# ArcadeRpiSmartShield_33_MCU.net
KiCad netlist of a schematic drawn in Altium Designer
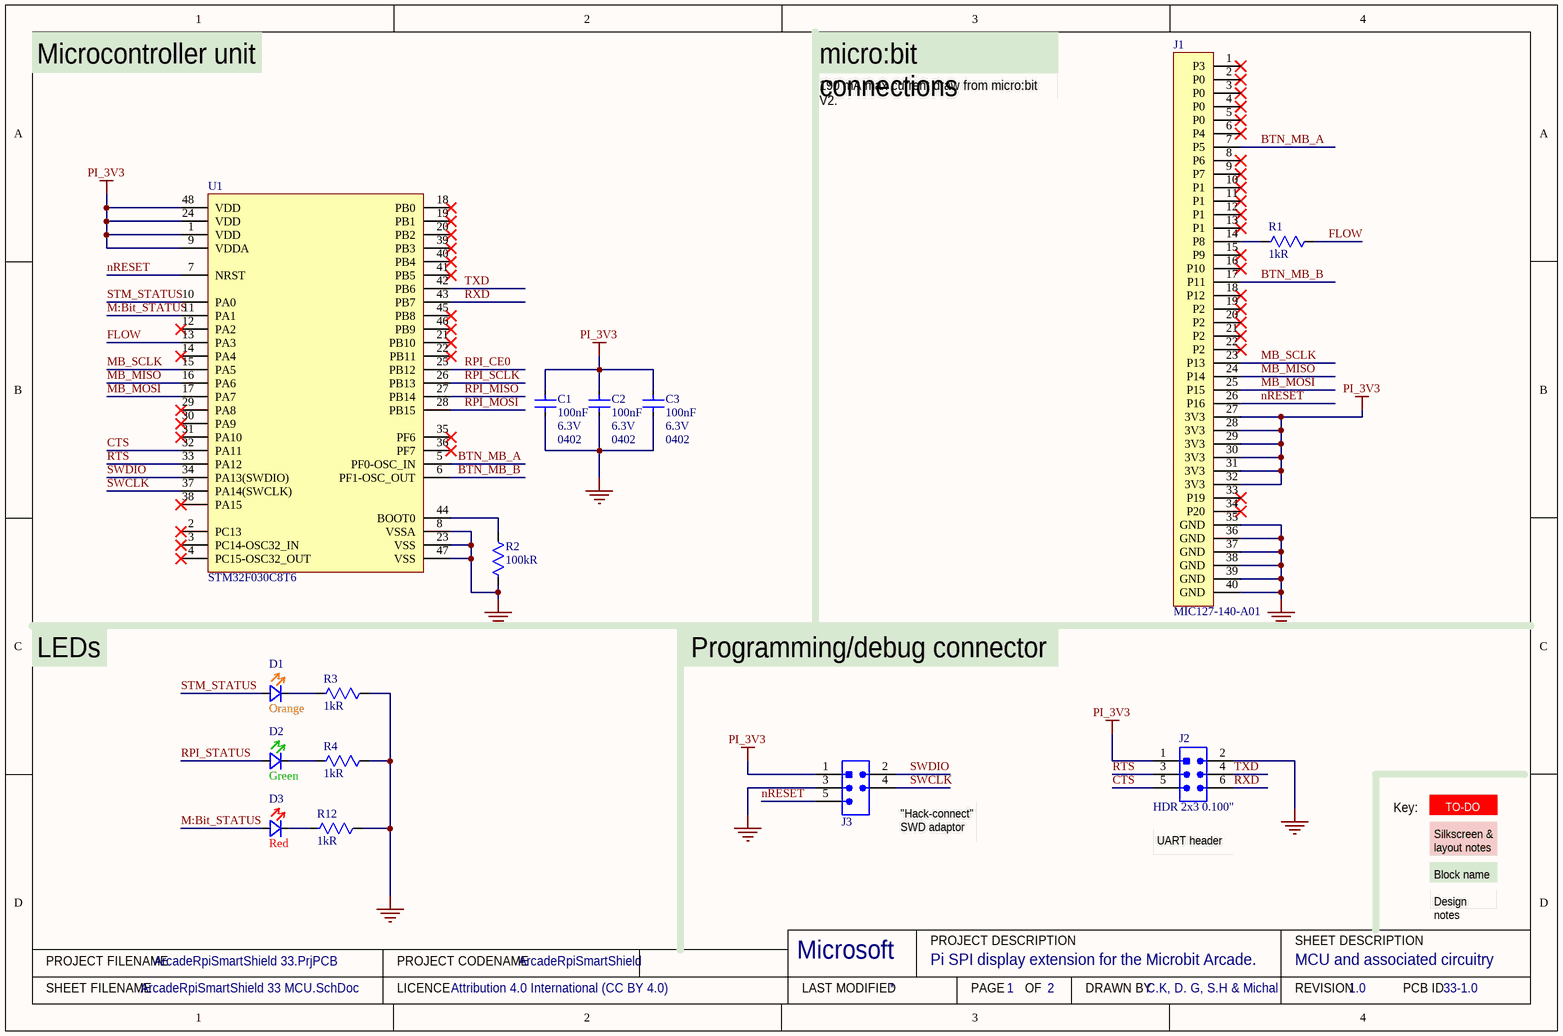
[diagram p0: ArcadeRpiSmartShield 33 MCU.SchDoc]

(export (version "E")
  (design (tool "Eeschema 10.0.6"))
  (components
    (comp (ref "C1")
      (value "CL05B104KQ5NNNC")
      (footprint "C0402_0.55MM - without outline")
      (description "CAP CER 0.1UF 6.3V X7R 0402")
      (fields
        (field (name "MANUFACTURER") "Samsung")
        (field (name "TOLERANCE") "10%")
        (field (name "CAPACITANCE") "100nF")
        (field (name "VOLTAGE RATING") "6.3V")
        (field (name "CASE CODE (IMPERIAL)") "0402")
        (field (name "CREATED BY") "D. Gakure")
        (field (name "CHECKED BY") "?")
      )
      (libsource (lib "Samsung") (part "CL05B104KQ5NNNC"))
    )
    (comp (ref "C2")
      (value "CL05B104KQ5NNNC")
      (footprint "C0402_0.55MM - without outline")
      (description "CAP CER 0.1UF 6.3V X7R 0402")
      (fields
        (field (name "MANUFACTURER") "Samsung")
        (field (name "TOLERANCE") "10%")
        (field (name "CAPACITANCE") "100nF")
        (field (name "VOLTAGE RATING") "6.3V")
        (field (name "CASE CODE (IMPERIAL)") "0402")
        (field (name "CREATED BY") "D. Gakure")
        (field (name "CHECKED BY") "?")
      )
      (libsource (lib "Samsung") (part "CL05B104KQ5NNNC"))
    )
    (comp (ref "C3")
      (value "CL05B104KQ5NNNC")
      (footprint "C0402_0.55MM - without outline")
      (description "CAP CER 0.1UF 6.3V X7R 0402")
      (fields
        (field (name "MANUFACTURER") "Samsung")
        (field (name "TOLERANCE") "10%")
        (field (name "CAPACITANCE") "100nF")
        (field (name "VOLTAGE RATING") "6.3V")
        (field (name "CASE CODE (IMPERIAL)") "0402")
        (field (name "CREATED BY") "D. Gakure")
        (field (name "CHECKED BY") "?")
      )
      (libsource (lib "Samsung") (part "CL05B104KQ5NNNC"))
    )
    (comp (ref "D1")
      (value "SML-D12D")
      (footprint "Rohm SML-D12 Orange - without outline")
      (description "1.6 x 0.8 x 0.55mm (0603) LED 605nm Orange")
      (fields
        (field (name "MANUFACTURER") "Rohm Semiconductor")
        (field (name "MANUFACTURER PART NUMBER") "SML-D12D8WT86")
        (field (name "COLOUR") "Orange")
      )
      (libsource (lib "Rohm") (part "SML-D12D"))
    )
    (comp (ref "D2")
      (value "SML-D12P")
      (footprint "Rohm SML-D12 Green - without outline")
      (description "1.6 x 0.8 x 0.55mm (0603) LED 560nm Green")
      (fields
        (field (name "MANUFACTURER") "Rohm Semiconductor")
        (field (name "MANUFACTURER PART NUMBER") "SML-D12P8WT86")
        (field (name "COLOUR") "Green")
      )
      (libsource (lib "Rohm") (part "SML-D12P"))
    )
    (comp (ref "D3")
      (value "SML-D12U")
      (footprint "Rohm SML-D12 Red - without outline")
      (description "1.6 x 0.8 x 0.55mm (0603) LED 620nm Red")
      (fields
        (field (name "MANUFACTURER") "Rohm Semiconductor")
        (field (name "MANUFACTURER PART NUMBER") "SML-D12U8WT86")
        (field (name "COLOUR") "Red")
      )
      (libsource (lib "Rohm") (part "SML-D12U"))
    )
    (comp (ref "J1")
      (value "Right Angle 1x40p 1.27 mm pitch edge connector for the micro:bit")
      (footprint "MIC127-140-A01")
      (description "\"Right Angle\" 1x40p 1.27mm Dongguan Yuliang BBC micro:bit edge connector")
      (fields
        (field (name "MANUFACTURER") "Dongguan Yuliang")
        (field (name "MANUFACTURER PART NUMBER") "MIC127-140-A01")
      )
      (libsource (lib "Yuliang") (part "MIC127-140-A01"))
    )
    (comp (ref "J2")
      (value "HDR 2x3 0.100\"")
      (footprint "PREC003DFAN-RC")
      (description "CONN HEADER VERT 6POS 2.54MM")
      (fields
        (field (name "MANUFACTURER") "Sullins")
        (field (name "MANUFACTURER PART NUMBER") "PREC003DFAN-RC")
        (field (name "CREATED BY") "D. Gakure")
        (field (name "CHECKED BY") "?")
      )
      (libsource (lib "SullinsConnectorSolutions") (part "PREC003DFAN-RC"))
    )
    (comp (ref "J3")
      (value "Hack Connect Mini 1.27 mm pitch 2-row")
      (footprint "HACK_CONNECT_MINI_5_X_1_27")
      (libsource (lib "generic-con") (part "HACK_CONNECT_MINI"))
    )
    (comp (ref "R1")
      (value "RC0402FR-071KL")
      (footprint "R0402 - Without outline")
      (description "RES SMD 1K OHM 1% 1/16W 0402")
      (fields
        (field (name "MANUFACTURER") "Yageo")
        (field (name "TOLERANCE") "1%")
        (field (name "RESISTANCE") "1kR")
        (field (name "CREATED") "D.G")
        (field (name "CHECKED") "?")
      )
      (libsource (lib "Yageo") (part "RC0402FR-071KL"))
    )
    (comp (ref "R2")
      (value "RC0402FR-07100KL")
      (footprint "R0402 - Without outline")
      (description "RES SMD 100K OHM 1% 1/16W 0402")
      (fields
        (field (name "MANUFACTURER") "Yageo")
        (field (name "RESISTANCE") "100kR")
        (field (name "TOLERANCE") "1%")
        (field (name "CREATED BY") "DG")
        (field (name "CHECKED BY") "?")
      )
      (libsource (lib "Yageo") (part "RC0402FR-07100KL"))
    )
    (comp (ref "R3")
      (value "RC0402FR-071KL")
      (footprint "R0402 - Without outline")
      (description "RES SMD 1K OHM 1% 1/16W 0402")
      (fields
        (field (name "MANUFACTURER") "Yageo")
        (field (name "TOLERANCE") "1%")
        (field (name "RESISTANCE") "1kR")
        (field (name "CREATED") "D.G")
        (field (name "CHECKED") "?")
      )
      (libsource (lib "Yageo") (part "RC0402FR-071KL"))
    )
    (comp (ref "R4")
      (value "RC0402FR-071KL")
      (footprint "R0402 - Without outline")
      (description "RES SMD 1K OHM 1% 1/16W 0402")
      (fields
        (field (name "MANUFACTURER") "Yageo")
        (field (name "TOLERANCE") "1%")
        (field (name "RESISTANCE") "1kR")
        (field (name "CREATED") "D.G")
        (field (name "CHECKED") "?")
      )
      (libsource (lib "Yageo") (part "RC0402FR-071KL"))
    )
    (comp (ref "R12")
      (value "RC0402FR-071KL")
      (footprint "R0402 - Without outline")
      (description "RES SMD 1K OHM 1% 1/16W 0402")
      (fields
        (field (name "MANUFACTURER") "Yageo")
        (field (name "TOLERANCE") "1%")
        (field (name "RESISTANCE") "1kR")
        (field (name "CREATED") "D.G")
        (field (name "CHECKED") "?")
      )
      (libsource (lib "Yageo") (part "RC0402FR-071KL"))
    )
    (comp (ref "U1")
      (value "STM32F030C8T6")
      (footprint "48-LQFP (7x7)")
      (description "MCU 32-bit STM32F ARM Cortex M0 RISC 64KB Flash 2.5V/3.3V 48-Pin LQFP Tray")
      (fields
        (field (name "MANUFACTURER") "STMicroelectronics")
        (field (name "MANUFACTURER PART NUMBER") "STM32F030C8T6")
        (field (name "CREATED BY") "D. Gakure")
        (field (name "CHECKED BY") "?")
      )
      (libsource (lib "ST") (part "STM32F030C8T6"))
    )
  )
  (nets
    (net (code "1") (name "/BTN_MB_A") (class "Default")
      (node (ref "J1") (pin "7") (pinfunction "P5_7") (pintype "passive"))
      (node (ref "U1") (pin "5") (pinfunction "PF0-OSC_IN_5") (pintype "passive"))
    )
    (net (code "2") (name "/BTN_MB_B") (class "Default")
      (node (ref "J1") (pin "17") (pinfunction "P11_17") (pintype "passive"))
      (node (ref "U1") (pin "6") (pinfunction "PF1-OSC_OUT_6") (pintype "passive"))
    )
    (net (code "3") (name "/CTS") (class "Default")
      (node (ref "J2") (pin "5") (pinfunction "RESET_5") (pintype "passive"))
      (node (ref "U1") (pin "32") (pinfunction "PA11_32") (pintype "passive"))
    )
    (net (code "4") (name "/FLOW") (class "Default")
      (node (ref "R1") (pin "1") (pinfunction "1_1") (pintype "passive"))
      (node (ref "U1") (pin "13") (pinfunction "PA3_13") (pintype "passive"))
    )
    (net (code "5") (name "/M:Bit_STATUS") (class "Default")
      (node (ref "D3") (pin "2") (pinfunction "A_2") (pintype "passive"))
      (node (ref "U1") (pin "11") (pinfunction "PA1_11") (pintype "passive"))
    )
    (net (code "6") (name "/MB_MISO") (class "Default")
      (node (ref "J1") (pin "24") (pinfunction "P14_24") (pintype "passive"))
      (node (ref "U1") (pin "16") (pinfunction "PA6_16") (pintype "passive"))
    )
    (net (code "7") (name "/MB_MOSI") (class "Default")
      (node (ref "J1") (pin "25") (pinfunction "P15_25") (pintype "passive"))
      (node (ref "U1") (pin "17") (pinfunction "PA7_17") (pintype "passive"))
    )
    (net (code "8") (name "/MB_SCLK") (class "Default")
      (node (ref "J1") (pin "23") (pinfunction "P13_23") (pintype "passive"))
      (node (ref "U1") (pin "15") (pinfunction "PA5_15") (pintype "passive"))
    )
    (net (code "9") (name "/RPI_CE0") (class "Default")
      (node (ref "U1") (pin "25") (pinfunction "PB12_25") (pintype "passive"))
    )
    (net (code "10") (name "/RPI_MISO") (class "Default")
      (node (ref "U1") (pin "27") (pinfunction "PB14_27") (pintype "passive"))
    )
    (net (code "11") (name "/RPI_MOSI") (class "Default")
      (node (ref "U1") (pin "28") (pinfunction "PB15_28") (pintype "passive"))
    )
    (net (code "12") (name "/RPI_SCLK") (class "Default")
      (node (ref "U1") (pin "26") (pinfunction "PB13_26") (pintype "passive"))
    )
    (net (code "13") (name "/RPI_STATUS") (class "Default")
      (node (ref "D2") (pin "2") (pinfunction "A_2") (pintype "passive"))
    )
    (net (code "14") (name "/RTS") (class "Default")
      (node (ref "J2") (pin "3") (pinfunction "GND_3") (pintype "passive"))
      (node (ref "U1") (pin "33") (pinfunction "PA12_33") (pintype "passive"))
    )
    (net (code "15") (name "/RXD") (class "Default")
      (node (ref "J2") (pin "6") (pinfunction "6_6") (pintype "passive"))
      (node (ref "U1") (pin "43") (pinfunction "PB7_43") (pintype "passive"))
    )
    (net (code "16") (name "/STM_STATUS") (class "Default")
      (node (ref "D1") (pin "2") (pinfunction "A_2") (pintype "passive"))
      (node (ref "U1") (pin "10") (pinfunction "PA0_10") (pintype "passive"))
    )
    (net (code "17") (name "/SWCLK") (class "Default")
      (node (ref "J3") (pin "4") (pinfunction "SWCLK_4") (pintype "passive"))
      (node (ref "U1") (pin "37") (pinfunction "PA14(SWCLK)_37") (pintype "passive"))
    )
    (net (code "18") (name "/SWDIO") (class "Default")
      (node (ref "J3") (pin "2") (pinfunction "SWDIO_2") (pintype "passive"))
      (node (ref "U1") (pin "34") (pinfunction "PA13(SWDIO)_34") (pintype "passive"))
    )
    (net (code "19") (name "/TXD") (class "Default")
      (node (ref "J2") (pin "4") (pinfunction "SWCLK_4") (pintype "passive"))
      (node (ref "U1") (pin "42") (pinfunction "PB6_42") (pintype "passive"))
    )
    (net (code "20") (name "/nRESET") (class "Default")
      (node (ref "J1") (pin "26") (pinfunction "P16_26") (pintype "passive"))
      (node (ref "J3") (pin "5") (pinfunction "RESET_5") (pintype "passive"))
      (node (ref "U1") (pin "7") (pinfunction "NRST_7") (pintype "passive"))
    )
    (net (code "21") (name "GND") (class "Default")
      (node (ref "C1") (pin "1") (pinfunction "1_1") (pintype "passive"))
      (node (ref "C2") (pin "1") (pinfunction "1_1") (pintype "passive"))
      (node (ref "C3") (pin "1") (pinfunction "1_1") (pintype "passive"))
      (node (ref "J1") (pin "35") (pinfunction "GND_35") (pintype "passive"))
      (node (ref "J1") (pin "36") (pinfunction "GND_36") (pintype "passive"))
      (node (ref "J1") (pin "37") (pinfunction "GND_37") (pintype "passive"))
      (node (ref "J1") (pin "38") (pinfunction "GND_38") (pintype "passive"))
      (node (ref "J1") (pin "39") (pinfunction "GND_39") (pintype "passive"))
      (node (ref "J1") (pin "40") (pinfunction "GND_40") (pintype "passive"))
      (node (ref "J2") (pin "2") (pinfunction "SWDIO_2") (pintype "passive"))
      (node (ref "J3") (pin "3") (pinfunction "GND_3") (pintype "passive"))
      (node (ref "R12") (pin "1") (pinfunction "1_1") (pintype "passive"))
      (node (ref "R2") (pin "1") (pinfunction "1_1") (pintype "passive"))
      (node (ref "R3") (pin "1") (pinfunction "1_1") (pintype "passive"))
      (node (ref "R4") (pin "1") (pinfunction "1_1") (pintype "passive"))
      (node (ref "U1") (pin "23") (pinfunction "VSS_23") (pintype "passive"))
      (node (ref "U1") (pin "47") (pinfunction "VSS_47") (pintype "passive"))
      (node (ref "U1") (pin "8") (pinfunction "VSSA_8") (pintype "passive"))
    )
    (net (code "22") (name "Net-(D1-K)") (class "Default")
      (node (ref "D1") (pin "1") (pinfunction "K_1") (pintype "passive"))
      (node (ref "R3") (pin "2") (pinfunction "2_2") (pintype "passive"))
    )
    (net (code "23") (name "Net-(D2-K)") (class "Default")
      (node (ref "D2") (pin "1") (pinfunction "K_1") (pintype "passive"))
      (node (ref "R4") (pin "2") (pinfunction "2_2") (pintype "passive"))
    )
    (net (code "24") (name "Net-(D3-K)") (class "Default")
      (node (ref "D3") (pin "1") (pinfunction "K_1") (pintype "passive"))
      (node (ref "R12") (pin "2") (pinfunction "2_2") (pintype "passive"))
    )
    (net (code "25") (name "Net-(J1-P8)") (class "Default")
      (node (ref "J1") (pin "14") (pinfunction "P8_14") (pintype "passive"))
      (node (ref "R1") (pin "2") (pinfunction "2_2") (pintype "passive"))
    )
    (net (code "26") (name "Net-(U1-BOOT0)") (class "Default")
      (node (ref "R2") (pin "2") (pinfunction "2_2") (pintype "passive"))
      (node (ref "U1") (pin "44") (pinfunction "BOOT0_44") (pintype "passive"))
    )
    (net (code "27") (name "PI_3V3") (class "Default")
      (node (ref "C1") (pin "2") (pinfunction "2_2") (pintype "passive"))
      (node (ref "C2") (pin "2") (pinfunction "2_2") (pintype "passive"))
      (node (ref "C3") (pin "2") (pinfunction "2_2") (pintype "passive"))
      (node (ref "J1") (pin "27") (pinfunction "3V3_27") (pintype "passive"))
      (node (ref "J1") (pin "28") (pinfunction "3V3_28") (pintype "passive"))
      (node (ref "J1") (pin "29") (pinfunction "3V3_29") (pintype "passive"))
      (node (ref "J1") (pin "30") (pinfunction "3V3_30") (pintype "passive"))
      (node (ref "J1") (pin "31") (pinfunction "3V3_31") (pintype "passive"))
      (node (ref "J1") (pin "32") (pinfunction "3V3_32") (pintype "passive"))
      (node (ref "J2") (pin "1") (pinfunction "VCC_1") (pintype "passive"))
      (node (ref "J3") (pin "1") (pinfunction "VCC_1") (pintype "passive"))
      (node (ref "U1") (pin "1") (pinfunction "VDD_1") (pintype "passive"))
      (node (ref "U1") (pin "24") (pinfunction "VDD_24") (pintype "passive"))
      (node (ref "U1") (pin "48") (pinfunction "VDD_48") (pintype "passive"))
      (node (ref "U1") (pin "9") (pinfunction "VDDA_9") (pintype "passive"))
    )
    (net (code "28") (name "unconnected-(J1-P0-Pad2)") (class "Default")
      (node (ref "J1") (pin "2") (pinfunction "P0_2") (pintype "passive+no_connect"))
    )
    (net (code "29") (name "unconnected-(J1-P0-Pad3)") (class "Default")
      (node (ref "J1") (pin "3") (pinfunction "P0_3") (pintype "passive+no_connect"))
    )
    (net (code "30") (name "unconnected-(J1-P0-Pad4)") (class "Default")
      (node (ref "J1") (pin "4") (pinfunction "P0_4") (pintype "passive+no_connect"))
    )
    (net (code "31") (name "unconnected-(J1-P0-Pad5)") (class "Default")
      (node (ref "J1") (pin "5") (pinfunction "P0_5") (pintype "passive+no_connect"))
    )
    (net (code "32") (name "unconnected-(J1-P1-Pad10)") (class "Default")
      (node (ref "J1") (pin "10") (pinfunction "P1_10") (pintype "passive+no_connect"))
    )
    (net (code "33") (name "unconnected-(J1-P1-Pad11)") (class "Default")
      (node (ref "J1") (pin "11") (pinfunction "P1_11") (pintype "passive+no_connect"))
    )
    (net (code "34") (name "unconnected-(J1-P1-Pad12)") (class "Default")
      (node (ref "J1") (pin "12") (pinfunction "P1_12") (pintype "passive+no_connect"))
    )
    (net (code "35") (name "unconnected-(J1-P1-Pad13)") (class "Default")
      (node (ref "J1") (pin "13") (pinfunction "P1_13") (pintype "passive+no_connect"))
    )
    (net (code "36") (name "unconnected-(J1-P2-Pad19)") (class "Default")
      (node (ref "J1") (pin "19") (pinfunction "P2_19") (pintype "passive+no_connect"))
    )
    (net (code "37") (name "unconnected-(J1-P2-Pad20)") (class "Default")
      (node (ref "J1") (pin "20") (pinfunction "P2_20") (pintype "passive+no_connect"))
    )
    (net (code "38") (name "unconnected-(J1-P2-Pad21)") (class "Default")
      (node (ref "J1") (pin "21") (pinfunction "P2_21") (pintype "passive+no_connect"))
    )
    (net (code "39") (name "unconnected-(J1-P2-Pad22)") (class "Default")
      (node (ref "J1") (pin "22") (pinfunction "P2_22") (pintype "passive+no_connect"))
    )
    (net (code "40") (name "unconnected-(J1-P3-Pad1)") (class "Default")
      (node (ref "J1") (pin "1") (pinfunction "P3_1") (pintype "passive+no_connect"))
    )
    (net (code "41") (name "unconnected-(J1-P4-Pad6)") (class "Default")
      (node (ref "J1") (pin "6") (pinfunction "P4_6") (pintype "passive+no_connect"))
    )
    (net (code "42") (name "unconnected-(J1-P6-Pad8)") (class "Default")
      (node (ref "J1") (pin "8") (pinfunction "P6_8") (pintype "passive+no_connect"))
    )
    (net (code "43") (name "unconnected-(J1-P7-Pad9)") (class "Default")
      (node (ref "J1") (pin "9") (pinfunction "P7_9") (pintype "passive+no_connect"))
    )
    (net (code "44") (name "unconnected-(J1-P9-Pad15)") (class "Default")
      (node (ref "J1") (pin "15") (pinfunction "P9_15") (pintype "passive+no_connect"))
    )
    (net (code "45") (name "unconnected-(J1-P10-Pad16)") (class "Default")
      (node (ref "J1") (pin "16") (pinfunction "P10_16") (pintype "passive+no_connect"))
    )
    (net (code "46") (name "unconnected-(J1-P12-Pad18)") (class "Default")
      (node (ref "J1") (pin "18") (pinfunction "P12_18") (pintype "passive+no_connect"))
    )
    (net (code "47") (name "unconnected-(J1-P19-Pad33)") (class "Default")
      (node (ref "J1") (pin "33") (pinfunction "P19_33") (pintype "passive+no_connect"))
    )
    (net (code "48") (name "unconnected-(J1-P20-Pad34)") (class "Default")
      (node (ref "J1") (pin "34") (pinfunction "P20_34") (pintype "passive+no_connect"))
    )
    (net (code "49") (name "unconnected-(U1-PA2-Pad12)") (class "Default")
      (node (ref "U1") (pin "12") (pinfunction "PA2_12") (pintype "passive+no_connect"))
    )
    (net (code "50") (name "unconnected-(U1-PA4-Pad14)") (class "Default")
      (node (ref "U1") (pin "14") (pinfunction "PA4_14") (pintype "passive+no_connect"))
    )
    (net (code "51") (name "unconnected-(U1-PA8-Pad29)") (class "Default")
      (node (ref "U1") (pin "29") (pinfunction "PA8_29") (pintype "passive+no_connect"))
    )
    (net (code "52") (name "unconnected-(U1-PA9-Pad30)") (class "Default")
      (node (ref "U1") (pin "30") (pinfunction "PA9_30") (pintype "passive+no_connect"))
    )
    (net (code "53") (name "unconnected-(U1-PA10-Pad31)") (class "Default")
      (node (ref "U1") (pin "31") (pinfunction "PA10_31") (pintype "passive+no_connect"))
    )
    (net (code "54") (name "unconnected-(U1-PA15-Pad38)") (class "Default")
      (node (ref "U1") (pin "38") (pinfunction "PA15_38") (pintype "passive+no_connect"))
    )
    (net (code "55") (name "unconnected-(U1-PB0-Pad18)") (class "Default")
      (node (ref "U1") (pin "18") (pinfunction "PB0_18") (pintype "passive+no_connect"))
    )
    (net (code "56") (name "unconnected-(U1-PB1-Pad19)") (class "Default")
      (node (ref "U1") (pin "19") (pinfunction "PB1_19") (pintype "passive+no_connect"))
    )
    (net (code "57") (name "unconnected-(U1-PB2-Pad20)") (class "Default")
      (node (ref "U1") (pin "20") (pinfunction "PB2_20") (pintype "passive+no_connect"))
    )
    (net (code "58") (name "unconnected-(U1-PB3-Pad39)") (class "Default")
      (node (ref "U1") (pin "39") (pinfunction "PB3_39") (pintype "passive+no_connect"))
    )
    (net (code "59") (name "unconnected-(U1-PB4-Pad40)") (class "Default")
      (node (ref "U1") (pin "40") (pinfunction "PB4_40") (pintype "passive+no_connect"))
    )
    (net (code "60") (name "unconnected-(U1-PB5-Pad41)") (class "Default")
      (node (ref "U1") (pin "41") (pinfunction "PB5_41") (pintype "passive+no_connect"))
    )
    (net (code "61") (name "unconnected-(U1-PB8-Pad45)") (class "Default")
      (node (ref "U1") (pin "45") (pinfunction "PB8_45") (pintype "passive+no_connect"))
    )
    (net (code "62") (name "unconnected-(U1-PB9-Pad46)") (class "Default")
      (node (ref "U1") (pin "46") (pinfunction "PB9_46") (pintype "passive+no_connect"))
    )
    (net (code "63") (name "unconnected-(U1-PB10-Pad21)") (class "Default")
      (node (ref "U1") (pin "21") (pinfunction "PB10_21") (pintype "passive+no_connect"))
    )
    (net (code "64") (name "unconnected-(U1-PB11-Pad22)") (class "Default")
      (node (ref "U1") (pin "22") (pinfunction "PB11_22") (pintype "passive+no_connect"))
    )
    (net (code "65") (name "unconnected-(U1-PC13-Pad2)") (class "Default")
      (node (ref "U1") (pin "2") (pinfunction "PC13_2") (pintype "passive+no_connect"))
    )
    (net (code "66") (name "unconnected-(U1-PC14-OSC32_IN-Pad3)") (class "Default")
      (node (ref "U1") (pin "3") (pinfunction "PC14-OSC32_IN_3") (pintype "passive+no_connect"))
    )
    (net (code "67") (name "unconnected-(U1-PC15-OSC32_OUT-Pad4)") (class "Default")
      (node (ref "U1") (pin "4") (pinfunction "PC15-OSC32_OUT_4") (pintype "passive+no_connect"))
    )
    (net (code "68") (name "unconnected-(U1-PF6-Pad35)") (class "Default")
      (node (ref "U1") (pin "35") (pinfunction "PF6_35") (pintype "passive+no_connect"))
    )
    (net (code "69") (name "unconnected-(U1-PF7-Pad36)") (class "Default")
      (node (ref "U1") (pin "36") (pinfunction "PF7_36") (pintype "passive+no_connect"))
    )
  )
)
